# WS2812B-module.net
KiCad netlist of a schematic drawn in EAGLE
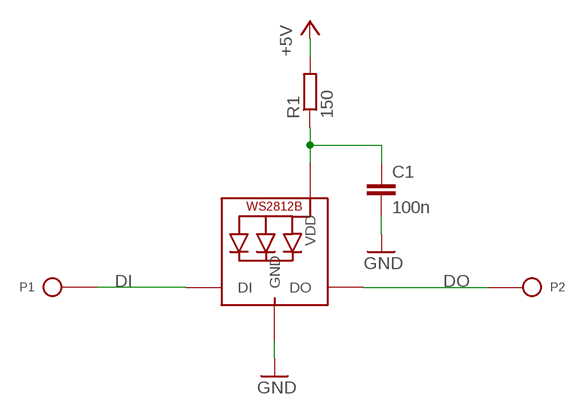
[diagram p0: schematic, sheet 1]

(export (version "E")
  (design (tool "Eeschema 10.0.6"))
  (components
    (comp (ref "C1")
      (value "100n")
      (footprint "eagle-import:C0805")
      (libsource (lib "eagle-import") (part "C-EUC0805"))
    )
    (comp (ref "LED1")
      (value "WS2812B3535")
      (footprint "eagle-import:LED3535")
      (libsource (lib "eagle-import") (part "WS2812B3535"))
    )
    (comp (ref "P1")
      (value "RUPAVELIKA")
      (footprint "eagle-import:RUPA2.54")
      (libsource (lib "eagle-import") (part "RUPAVELIKA"))
    )
    (comp (ref "P2")
      (value "RUPAVELIKA")
      (footprint "eagle-import:RUPA2.54")
      (libsource (lib "eagle-import") (part "RUPAVELIKA"))
    )
    (comp (ref "R1")
      (value "150")
      (footprint "eagle-import:R0805")
      (libsource (lib "eagle-import") (part "R-EU_R0805"))
    )
  )
  (nets
    (net (code "1") (name "+5V") (class "Default")
      (node (ref "R1") (pin "2") (pinfunction "2_2") (pintype "passive"))
    )
    (net (code "2") (name "/DI") (class "Default")
      (node (ref "LED1") (pin "1") (pinfunction "DI_1") (pintype "input"))
      (node (ref "P1") (pin "P$1") (pinfunction "P_P$1") (pintype "bidirectional"))
    )
    (net (code "3") (name "/DO") (class "Default")
      (node (ref "LED1") (pin "3") (pinfunction "DO_3") (pintype "output"))
      (node (ref "P2") (pin "P$1") (pinfunction "P_P$1") (pintype "bidirectional"))
    )
    (net (code "4") (name "GND") (class "Default")
      (node (ref "C1") (pin "2") (pinfunction "2_2") (pintype "passive"))
      (node (ref "LED1") (pin "4") (pinfunction "GND_4") (pintype "power_in"))
    )
    (net (code "5") (name "Net-(LED1-VDD)") (class "Default")
      (node (ref "C1") (pin "1") (pinfunction "1_1") (pintype "passive"))
      (node (ref "LED1") (pin "2") (pinfunction "VDD_2") (pintype "power_in"))
      (node (ref "R1") (pin "1") (pinfunction "1_1") (pintype "passive"))
    )
  )
)
